# Schemat.net
KiCad netlist of a schematic drawn in Altium Designer
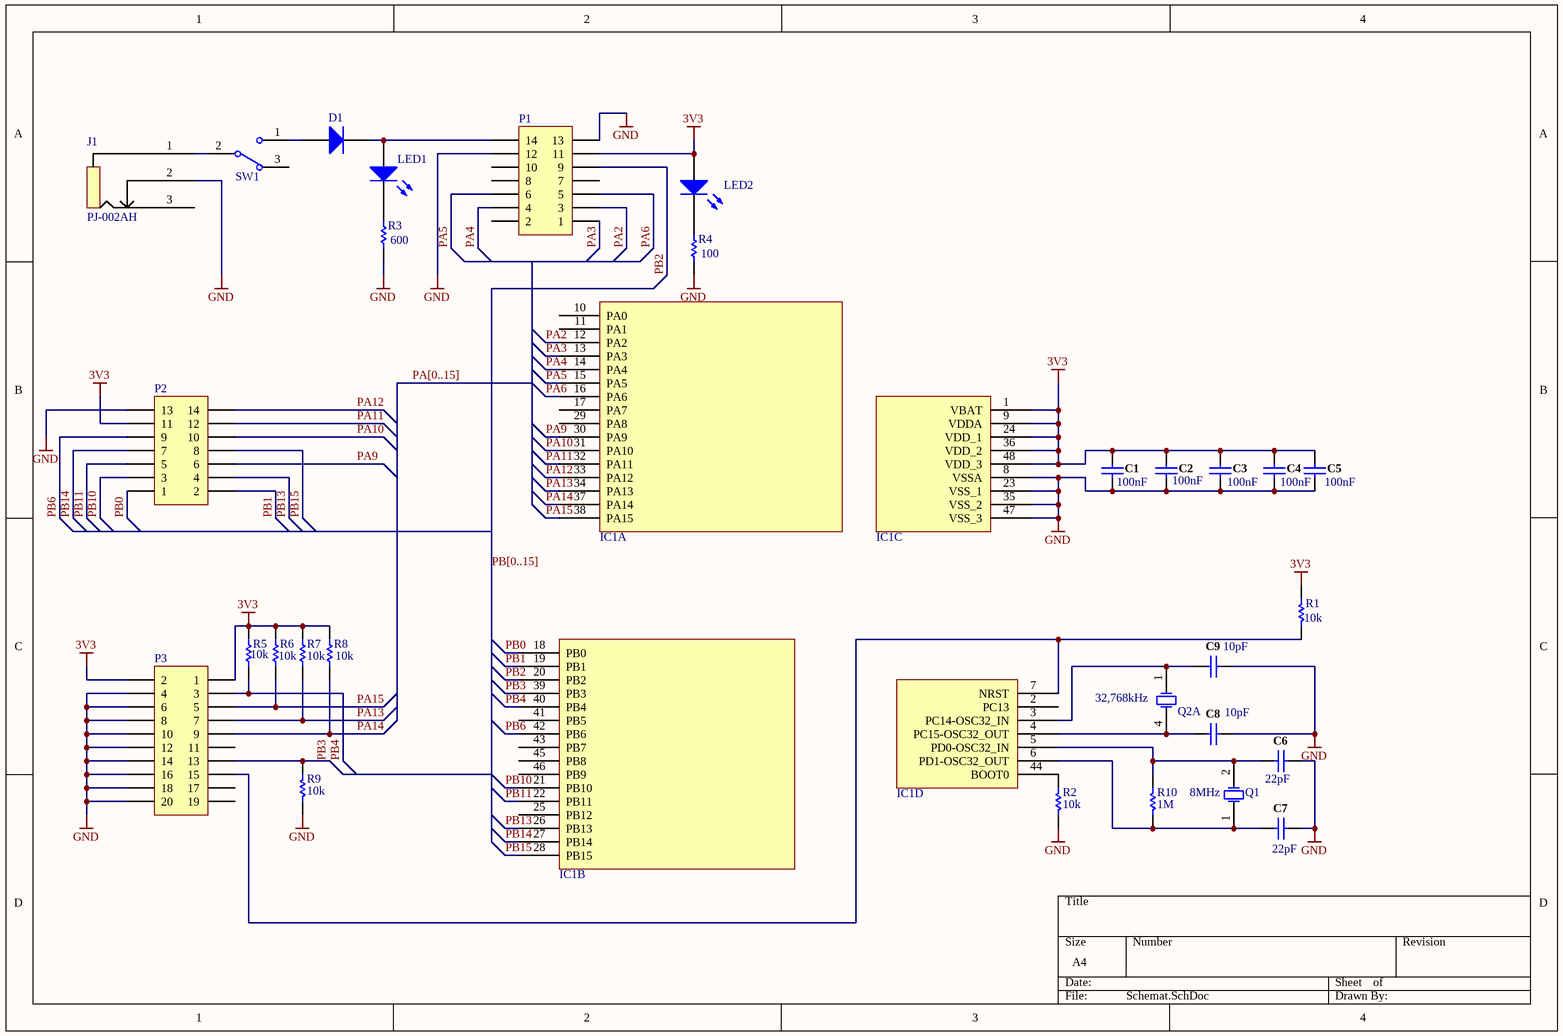
[diagram p0: Schemat.SchDoc]

(export (version "E")
  (design (tool "Eeschema 10.0.6"))
  (components
    (comp (ref "C1")
      (value "Comment")
      (description "Capacitor, Non-Polarized")
      (fields (field (name "C") "100nF"))
      (libsource (lib "CAP-NP") (part "CAP-NP"))
    )
    (comp (ref "C2")
      (value "Comment")
      (description "Capacitor, Non-Polarized")
      (fields (field (name "C") "100nF"))
      (libsource (lib "CAP-NP") (part "CAP-NP"))
    )
    (comp (ref "C3")
      (value "Comment")
      (description "Capacitor, Non-Polarized")
      (fields (field (name "C") "100nF"))
      (libsource (lib "CAP-NP") (part "CAP-NP"))
    )
    (comp (ref "C4")
      (value "Comment")
      (description "Capacitor, Non-Polarized")
      (fields (field (name "C") "100nF"))
      (libsource (lib "CAP-NP") (part "CAP-NP"))
    )
    (comp (ref "C5")
      (value "Comment")
      (description "Capacitor, Non-Polarized")
      (fields (field (name "C") "100nF"))
      (libsource (lib "CAP-NP") (part "CAP-NP"))
    )
    (comp (ref "C6")
      (value "Comment")
      (description "Capacitor, Non-Polarized")
      (fields (field (name "C") "22pF"))
      (libsource (lib "CAP-NP") (part "CAP-NP"))
    )
    (comp (ref "C7")
      (value "Comment")
      (description "Capacitor, Non-Polarized")
      (fields (field (name "C") "22pF"))
      (libsource (lib "CAP-NP") (part "CAP-NP"))
    )
    (comp (ref "C8")
      (value "Comment")
      (description "Capacitor, Non-Polarized")
      (fields (field (name "C") "10pF"))
      (libsource (lib "CAP-NP") (part "CAP-NP"))
    )
    (comp (ref "C9")
      (value "Comment")
      (description "Capacitor, Non-Polarized")
      (fields (field (name "C") "10pF"))
      (libsource (lib "CAP-NP") (part "CAP-NP"))
    )
    (comp (ref "D1") (value "Comment") (libsource (lib "KESE-D_K1A2-2") (part "KESE-D_K1A2-2")))
    (comp (ref "IC1")
      (value "Comment")
      (description "STM32F103C8T6")
      (libsource (lib "") (part "STM32F103C8T6_1"))
    )
    (comp (ref "J1")
      (value "PJ-002AH-SMT")
      (description "DC Power Jack")
      (fields (field (name "SUPPLIER PART NUMBER 1") "PJ-002AH"))
      (libsource (lib "Jack") (part "PJ-002AH-SMT"))
    )
    (comp (ref "LED1")
      (value "Comment")
      (footprint "3.2X1.6X1.1")
      (description "Typical RED, GREEN, YELLOW, AMBER GaAs LED")
      (fields (field (name "PUBLISHER") "Altium Limited"))
      (libsource (lib "Miscellaneous Devices") (part "LED2"))
    )
    (comp (ref "LED2")
      (value "Comment")
      (footprint "3.2X1.6X1.1")
      (description "Typical RED, GREEN, YELLOW, AMBER GaAs LED")
      (fields (field (name "PUBLISHER") "Altium Limited"))
      (libsource (lib "Miscellaneous Devices") (part "LED2"))
    )
    (comp (ref "P1")
      (value "Comment")
      (footprint "HDR2X7")
      (description "Header, 7-Pin, Dual row")
      (fields (field (name "PUBLISHER") "Altium Limited"))
      (libsource (lib "") (part "Header 7X2_1"))
    )
    (comp (ref "P2")
      (value "Comment")
      (footprint "HDR2X7")
      (description "Header, 7-Pin, Dual row")
      (fields (field (name "PUBLISHER") "Altium Limited"))
      (libsource (lib "Miscellaneous Connectors") (part "Header 7X2"))
    )
    (comp (ref "P3")
      (value "Comment")
      (footprint "HDR2X10")
      (description "Header, 10-Pin, Dual row")
      (fields (field (name "PUBLISHER") "Altium Limited"))
      (libsource (lib "Miscellaneous Connectors") (part "Header 10X2"))
    )
    (comp (ref "Q1")
      (value "Comment")
      (fields (field (name "F") "8MHz"))
      (libsource (lib "Altium Content Vault") (part "SYM-0089-00003-1"))
    )
    (comp (ref "Q2")
      (value "Comment")
      (fields (field (name "F") "32,768kHz"))
      (libsource (lib "Altium Content Vault") (part "SYM-0072-00001-3"))
    )
    (comp (ref "R1")
      (value "Comment")
      (fields (field (name "R") "10k"))
      (libsource (lib "Altium Content Vault") (part "SYM-0353-00001-1"))
    )
    (comp (ref "R2")
      (value "Comment")
      (fields (field (name "R") "10k"))
      (libsource (lib "Altium Content Vault") (part "SYM-0353-00001-1"))
    )
    (comp (ref "R3")
      (value "Comment")
      (fields (field (name "R") "600"))
      (libsource (lib "Altium Content Vault") (part "SYM-0353-00001-1"))
    )
    (comp (ref "R4")
      (value "Comment")
      (fields (field (name "R") "100"))
      (libsource (lib "Altium Content Vault") (part "SYM-0353-00001-1"))
    )
    (comp (ref "R5")
      (value "Comment")
      (fields (field (name "R") "10k"))
      (libsource (lib "Altium Content Vault") (part "SYM-0353-00001-1"))
    )
    (comp (ref "R6")
      (value "Comment")
      (fields (field (name "R") "10k"))
      (libsource (lib "Altium Content Vault") (part "SYM-0353-00001-1"))
    )
    (comp (ref "R7")
      (value "Comment")
      (fields (field (name "R") "10k"))
      (libsource (lib "Altium Content Vault") (part "SYM-0353-00001-1"))
    )
    (comp (ref "R8")
      (value "Comment")
      (fields (field (name "R") "10k"))
      (libsource (lib "Altium Content Vault") (part "SYM-0353-00001-1"))
    )
    (comp (ref "R9")
      (value "Comment")
      (fields (field (name "R") "10k"))
      (libsource (lib "Altium Content Vault") (part "SYM-0353-00001-1"))
    )
    (comp (ref "R10")
      (value "Comment")
      (fields (field (name "R") "1M"))
      (libsource (lib "Altium Content Vault") (part "SYM-0353-00001-1"))
    )
    (comp (ref "SW1") (value "Comment") (libsource (lib "SW-SPDT-3") (part "SW-SPDT-3")))
  )
  (nets
    (net (code "10") (name "/PA2") (class "Default")
      (node (ref "IC1") (pin "12") (pinfunction "PA2_12") (pintype "passive"))
      (node (ref "P1") (pin "3") (pinfunction "3_3") (pintype "passive"))
    )
    (net (code "11") (name "/PA3") (class "Default")
      (node (ref "IC1") (pin "13") (pinfunction "PA3_13") (pintype "passive"))
      (node (ref "P1") (pin "1") (pinfunction "1_1") (pintype "passive"))
    )
    (net (code "12") (name "/PA4") (class "Default")
      (node (ref "IC1") (pin "14") (pinfunction "PA4_14") (pintype "passive"))
      (node (ref "P1") (pin "4") (pinfunction "4_4") (pintype "passive"))
    )
    (net (code "13") (name "/PA5") (class "Default")
      (node (ref "IC1") (pin "15") (pinfunction "PA5_15") (pintype "passive"))
      (node (ref "P1") (pin "6") (pinfunction "6_6") (pintype "passive"))
    )
    (net (code "14") (name "/PA6") (class "Default")
      (node (ref "IC1") (pin "16") (pinfunction "PA6_16") (pintype "passive"))
      (node (ref "P1") (pin "5") (pinfunction "5_5") (pintype "passive"))
    )
    (net (code "15") (name "/PA9") (class "Default")
      (node (ref "IC1") (pin "30") (pinfunction "PA9_30") (pintype "passive"))
      (node (ref "P2") (pin "6") (pinfunction "6_6") (pintype "passive"))
    )
    (net (code "16") (name "/PA10") (class "Default")
      (node (ref "IC1") (pin "31") (pinfunction "PA10_31") (pintype "passive"))
      (node (ref "P2") (pin "10") (pinfunction "10_10") (pintype "passive"))
    )
    (net (code "17") (name "/PA11") (class "Default")
      (node (ref "IC1") (pin "32") (pinfunction "PA11_32") (pintype "passive"))
      (node (ref "P2") (pin "12") (pinfunction "12_12") (pintype "passive"))
    )
    (net (code "18") (name "/PA12") (class "Default")
      (node (ref "IC1") (pin "33") (pinfunction "PA12_33") (pintype "passive"))
      (node (ref "P2") (pin "14") (pinfunction "14_14") (pintype "passive"))
    )
    (net (code "19") (name "/PA13") (class "Default")
      (node (ref "IC1") (pin "34") (pinfunction "PA13_34") (pintype "passive"))
      (node (ref "P3") (pin "7") (pinfunction "7_7") (pintype "passive"))
      (node (ref "R7") (pin "1") (pinfunction "1_1") (pintype "passive"))
    )
    (net (code "20") (name "/PA14") (class "Default")
      (node (ref "IC1") (pin "37") (pinfunction "PA14_37") (pintype "passive"))
      (node (ref "P3") (pin "9") (pinfunction "9_9") (pintype "passive"))
      (node (ref "R8") (pin "1") (pinfunction "1_1") (pintype "passive"))
    )
    (net (code "21") (name "/PA15") (class "Default")
      (node (ref "IC1") (pin "38") (pinfunction "PA15_38") (pintype "passive"))
      (node (ref "P3") (pin "5") (pinfunction "5_5") (pintype "passive"))
      (node (ref "R6") (pin "1") (pinfunction "1_1") (pintype "passive"))
    )
    (net (code "23") (name "/PB0") (class "Default")
      (node (ref "IC1") (pin "18") (pinfunction "PB0_18") (pintype "passive"))
      (node (ref "P2") (pin "1") (pinfunction "1_1") (pintype "passive"))
    )
    (net (code "24") (name "/PB1") (class "Default")
      (node (ref "IC1") (pin "19") (pinfunction "PB1_19") (pintype "passive"))
      (node (ref "P2") (pin "2") (pinfunction "2_2") (pintype "passive"))
    )
    (net (code "25") (name "/PB2") (class "Default")
      (node (ref "IC1") (pin "20") (pinfunction "PB2_20") (pintype "passive"))
      (node (ref "P1") (pin "9") (pinfunction "9_9") (pintype "passive"))
    )
    (net (code "26") (name "/PB3") (class "Default")
      (node (ref "IC1") (pin "39") (pinfunction "PB3_39") (pintype "passive"))
      (node (ref "P3") (pin "13") (pinfunction "13_13") (pintype "passive"))
      (node (ref "R9") (pin "2") (pinfunction "2_2") (pintype "passive"))
    )
    (net (code "27") (name "/PB4") (class "Default")
      (node (ref "IC1") (pin "40") (pinfunction "PB4_40") (pintype "passive"))
      (node (ref "P3") (pin "3") (pinfunction "3_3") (pintype "passive"))
      (node (ref "R5") (pin "1") (pinfunction "1_1") (pintype "passive"))
    )
    (net (code "28") (name "/PB6") (class "Default")
      (node (ref "IC1") (pin "42") (pinfunction "PB6_42") (pintype "passive"))
      (node (ref "P2") (pin "9") (pinfunction "9_9") (pintype "passive"))
    )
    (net (code "29") (name "/PB10") (class "Default")
      (node (ref "IC1") (pin "21") (pinfunction "PB10_21") (pintype "passive"))
      (node (ref "P2") (pin "3") (pinfunction "3_3") (pintype "passive"))
    )
    (net (code "30") (name "/PB11") (class "Default")
      (node (ref "IC1") (pin "22") (pinfunction "PB11_22") (pintype "passive"))
      (node (ref "P2") (pin "5") (pinfunction "5_5") (pintype "passive"))
    )
    (net (code "31") (name "/PB13") (class "Default")
      (node (ref "IC1") (pin "26") (pinfunction "PB13_26") (pintype "passive"))
      (node (ref "P2") (pin "4") (pinfunction "4_4") (pintype "passive"))
    )
    (net (code "32") (name "/PB14") (class "Default")
      (node (ref "IC1") (pin "27") (pinfunction "PB14_27") (pintype "passive"))
      (node (ref "P2") (pin "7") (pinfunction "7_7") (pintype "passive"))
    )
    (net (code "33") (name "/PB15") (class "Default")
      (node (ref "IC1") (pin "28") (pinfunction "PB15_28") (pintype "passive"))
      (node (ref "P2") (pin "8") (pinfunction "8_8") (pintype "passive"))
    )
    (net (code "35") (name "3V3") (class "Default")
      (node (ref "C1") (pin "1") (pinfunction "1_1") (pintype "passive"))
      (node (ref "C2") (pin "1") (pinfunction "1_1") (pintype "passive"))
      (node (ref "C3") (pin "1") (pinfunction "1_1") (pintype "passive"))
      (node (ref "C4") (pin "1") (pinfunction "1_1") (pintype "passive"))
      (node (ref "C5") (pin "1") (pinfunction "1_1") (pintype "passive"))
      (node (ref "IC1") (pin "1") (pinfunction "VBAT_1") (pintype "passive"))
      (node (ref "IC1") (pin "24") (pinfunction "VDD_1_24") (pintype "passive"))
      (node (ref "IC1") (pin "36") (pinfunction "VDD_2_36") (pintype "passive"))
      (node (ref "IC1") (pin "48") (pinfunction "VDD_3_48") (pintype "passive"))
      (node (ref "IC1") (pin "9") (pinfunction "VDDA_9") (pintype "passive"))
      (node (ref "LED2") (pin "1") (pinfunction "A_1") (pintype "passive"))
      (node (ref "P1") (pin "11") (pinfunction "11_11") (pintype "passive"))
      (node (ref "P2") (pin "11") (pinfunction "11_11") (pintype "passive"))
      (node (ref "P3") (pin "1") (pinfunction "1_1") (pintype "passive"))
      (node (ref "P3") (pin "2") (pinfunction "2_2") (pintype "passive"))
      (node (ref "R1") (pin "2") (pinfunction "2_2") (pintype "passive"))
      (node (ref "R5") (pin "2") (pinfunction "2_2") (pintype "passive"))
      (node (ref "R6") (pin "2") (pinfunction "2_2") (pintype "passive"))
      (node (ref "R7") (pin "2") (pinfunction "2_2") (pintype "passive"))
      (node (ref "R8") (pin "2") (pinfunction "2_2") (pintype "passive"))
    )
    (net (code "36") (name "GND") (class "Default")
      (node (ref "C1") (pin "2") (pinfunction "2_2") (pintype "passive"))
      (node (ref "C2") (pin "2") (pinfunction "2_2") (pintype "passive"))
      (node (ref "C3") (pin "2") (pinfunction "2_2") (pintype "passive"))
      (node (ref "C4") (pin "2") (pinfunction "2_2") (pintype "passive"))
      (node (ref "C5") (pin "2") (pinfunction "2_2") (pintype "passive"))
      (node (ref "C6") (pin "1") (pinfunction "1_1") (pintype "passive"))
      (node (ref "C7") (pin "1") (pinfunction "1_1") (pintype "passive"))
      (node (ref "C8") (pin "1") (pinfunction "1_1") (pintype "passive"))
      (node (ref "C9") (pin "1") (pinfunction "1_1") (pintype "passive"))
      (node (ref "IC1") (pin "23") (pinfunction "VSS_1_23") (pintype "passive"))
      (node (ref "IC1") (pin "35") (pinfunction "VSS_2_35") (pintype "passive"))
      (node (ref "IC1") (pin "47") (pinfunction "VSS_3_47") (pintype "passive"))
      (node (ref "IC1") (pin "8") (pinfunction "VSSA_8") (pintype "passive"))
      (node (ref "J1") (pin "2") (pinfunction "2_2") (pintype "passive"))
      (node (ref "P1") (pin "12") (pinfunction "12_12") (pintype "passive"))
      (node (ref "P1") (pin "13") (pinfunction "13_13") (pintype "passive"))
      (node (ref "P2") (pin "13") (pinfunction "13_13") (pintype "passive"))
      (node (ref "P3") (pin "10") (pinfunction "10_10") (pintype "passive"))
      (node (ref "P3") (pin "12") (pinfunction "12_12") (pintype "passive"))
      (node (ref "P3") (pin "14") (pinfunction "14_14") (pintype "passive"))
      (node (ref "P3") (pin "16") (pinfunction "16_16") (pintype "passive"))
      (node (ref "P3") (pin "18") (pinfunction "18_18") (pintype "passive"))
      (node (ref "P3") (pin "20") (pinfunction "20_20") (pintype "passive"))
      (node (ref "P3") (pin "4") (pinfunction "4_4") (pintype "passive"))
      (node (ref "P3") (pin "6") (pinfunction "6_6") (pintype "passive"))
      (node (ref "P3") (pin "8") (pinfunction "8_8") (pintype "passive"))
      (node (ref "R2") (pin "2") (pinfunction "2_2") (pintype "passive"))
      (node (ref "R3") (pin "1") (pinfunction "1_1") (pintype "passive"))
      (node (ref "R4") (pin "1") (pinfunction "1_1") (pintype "passive"))
      (node (ref "R9") (pin "1") (pinfunction "1_1") (pintype "passive"))
    )
    (net (code "37") (name "Net-(D1-A)") (class "Default")
      (node (ref "D1") (pin "2") (pinfunction "A_2") (pintype "passive"))
      (node (ref "SW1") (pin "1") (pinfunction "1_1") (pintype "passive"))
    )
    (net (code "38") (name "Net-(D1-K)") (class "Default")
      (node (ref "D1") (pin "1") (pinfunction "K_1") (pintype "passive"))
      (node (ref "LED1") (pin "1") (pinfunction "A_1") (pintype "passive"))
      (node (ref "P1") (pin "14") (pinfunction "14_14") (pintype "passive"))
    )
    (net (code "39") (name "Net-(IC1D-BOOT0)") (class "Default")
      (node (ref "IC1") (pin "44") (pinfunction "BOOT0_44") (pintype "passive"))
      (node (ref "R2") (pin "1") (pinfunction "1_1") (pintype "passive"))
    )
    (net (code "40") (name "Net-(IC1D-NRST)") (class "Default")
      (node (ref "IC1") (pin "7") (pinfunction "NRST_7") (pintype "passive"))
      (node (ref "P3") (pin "15") (pinfunction "15_15") (pintype "passive"))
      (node (ref "R1") (pin "1") (pinfunction "1_1") (pintype "passive"))
    )
    (net (code "41") (name "Net-(IC1D-PC14-OSC32_IN)") (class "Default")
      (node (ref "C9") (pin "2") (pinfunction "2_2") (pintype "passive"))
      (node (ref "IC1") (pin "3") (pinfunction "PC14-OSC32_IN_3") (pintype "passive"))
      (node (ref "Q2") (pin "1") (pinfunction "X1_1") (pintype "passive"))
    )
    (net (code "42") (name "Net-(IC1D-PC15-OSC32_OUT)") (class "Default")
      (node (ref "C8") (pin "2") (pinfunction "2_2") (pintype "passive"))
      (node (ref "IC1") (pin "4") (pinfunction "PC15-OSC32_OUT_4") (pintype "passive"))
      (node (ref "Q2") (pin "4") (pinfunction "X2_4") (pintype "passive"))
    )
    (net (code "43") (name "Net-(IC1D-PD0-OSC32_IN)") (class "Default")
      (node (ref "C6") (pin "2") (pinfunction "2_2") (pintype "passive"))
      (node (ref "IC1") (pin "5") (pinfunction "PD0-OSC32_IN_5") (pintype "passive"))
      (node (ref "Q1") (pin "2") (pinfunction "X2_2") (pintype "passive"))
      (node (ref "R10") (pin "2") (pinfunction "2_2") (pintype "passive"))
    )
    (net (code "44") (name "Net-(IC1D-PD1-OSC32_OUT)") (class "Default")
      (node (ref "C7") (pin "2") (pinfunction "2_2") (pintype "passive"))
      (node (ref "IC1") (pin "6") (pinfunction "PD1-OSC32_OUT_6") (pintype "passive"))
      (node (ref "Q1") (pin "1") (pinfunction "X1_1") (pintype "passive"))
      (node (ref "R10") (pin "1") (pinfunction "1_1") (pintype "passive"))
    )
    (net (code "45") (name "Net-(J1-Pad1)") (class "Default")
      (node (ref "J1") (pin "1") (pinfunction "1_1") (pintype "passive"))
      (node (ref "SW1") (pin "2") (pinfunction "2_2") (pintype "passive"))
    )
    (net (code "46") (name "Net-(LED1-K)") (class "Default")
      (node (ref "LED1") (pin "2") (pinfunction "K_2") (pintype "passive"))
      (node (ref "R3") (pin "2") (pinfunction "2_2") (pintype "passive"))
    )
    (net (code "47") (name "Net-(LED2-K)") (class "Default")
      (node (ref "LED2") (pin "2") (pinfunction "K_2") (pintype "passive"))
      (node (ref "R4") (pin "2") (pinfunction "2_2") (pintype "passive"))
    )
    (net (code "48") (name "unconnected-(IC1A-PA0-Pad10)") (class "Default")
      (node (ref "IC1") (pin "10") (pinfunction "PA0_10") (pintype "passive"))
    )
    (net (code "49") (name "unconnected-(IC1A-PA1-Pad11)") (class "Default")
      (node (ref "IC1") (pin "11") (pinfunction "PA1_11") (pintype "passive"))
    )
    (net (code "50") (name "unconnected-(IC1A-PA7-Pad17)") (class "Default")
      (node (ref "IC1") (pin "17") (pinfunction "PA7_17") (pintype "passive"))
    )
    (net (code "51") (name "unconnected-(IC1A-PA8-Pad29)") (class "Default")
      (node (ref "IC1") (pin "29") (pinfunction "PA8_29") (pintype "passive"))
    )
    (net (code "52") (name "unconnected-(IC1B-PB5-Pad41)") (class "Default")
      (node (ref "IC1") (pin "41") (pinfunction "PB5_41") (pintype "passive"))
    )
    (net (code "53") (name "unconnected-(IC1B-PB7-Pad43)") (class "Default")
      (node (ref "IC1") (pin "43") (pinfunction "PB7_43") (pintype "passive"))
    )
    (net (code "54") (name "unconnected-(IC1B-PB8-Pad45)") (class "Default")
      (node (ref "IC1") (pin "45") (pinfunction "PB8_45") (pintype "passive"))
    )
    (net (code "55") (name "unconnected-(IC1B-PB9-Pad46)") (class "Default")
      (node (ref "IC1") (pin "46") (pinfunction "PB9_46") (pintype "passive"))
    )
    (net (code "56") (name "unconnected-(IC1B-PB12-Pad25)") (class "Default")
      (node (ref "IC1") (pin "25") (pinfunction "PB12_25") (pintype "passive"))
    )
    (net (code "57") (name "unconnected-(IC1D-PC13-Pad2)") (class "Default")
      (node (ref "IC1") (pin "2") (pinfunction "PC13_2") (pintype "passive"))
    )
    (net (code "58") (name "unconnected-(J1-Pad3)") (class "Default")
      (node (ref "J1") (pin "3") (pinfunction "3_3") (pintype "passive"))
    )
    (net (code "59") (name "unconnected-(P1-Pad2)") (class "Default")
      (node (ref "P1") (pin "2") (pinfunction "2_2") (pintype "passive"))
    )
    (net (code "60") (name "unconnected-(P1-Pad7)") (class "Default")
      (node (ref "P1") (pin "7") (pinfunction "7_7") (pintype "passive"))
    )
    (net (code "61") (name "unconnected-(P1-Pad8)") (class "Default")
      (node (ref "P1") (pin "8") (pinfunction "8_8") (pintype "passive"))
    )
    (net (code "62") (name "unconnected-(P1-Pad10)") (class "Default")
      (node (ref "P1") (pin "10") (pinfunction "10_10") (pintype "passive"))
    )
    (net (code "63") (name "unconnected-(P3-Pad11)") (class "Default")
      (node (ref "P3") (pin "11") (pinfunction "11_11") (pintype "passive"))
    )
    (net (code "64") (name "unconnected-(P3-Pad17)") (class "Default")
      (node (ref "P3") (pin "17") (pinfunction "17_17") (pintype "passive"))
    )
    (net (code "65") (name "unconnected-(P3-Pad19)") (class "Default")
      (node (ref "P3") (pin "19") (pinfunction "19_19") (pintype "passive"))
    )
    (net (code "66") (name "unconnected-(SW1-Pad3)") (class "Default")
      (node (ref "SW1") (pin "3") (pinfunction "3_3") (pintype "passive"))
    )
  )
)
